# MCU.net
KiCad netlist of a schematic drawn in Altium Designer
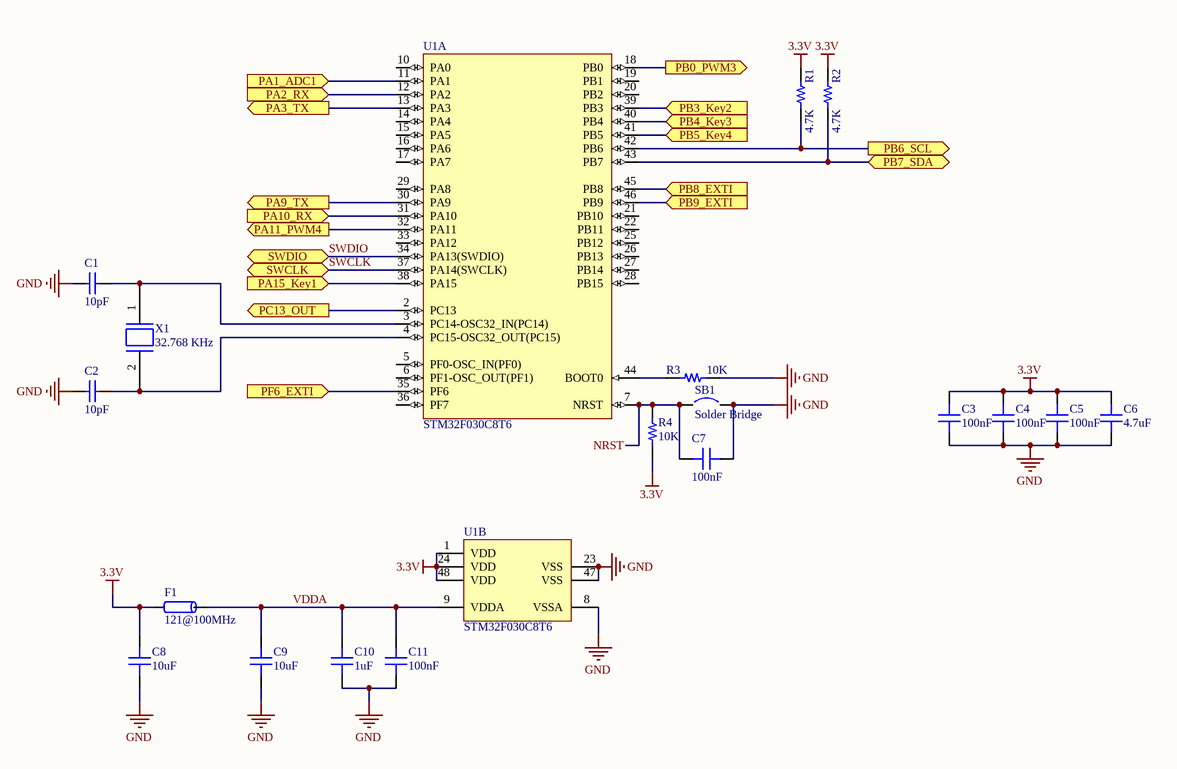
[diagram p0: MCU.SchDoc]

(export (version "E")
  (design (tool "Eeschema 10.0.6"))
  (components
    (comp (ref "C1")
      (value "10pF")
      (footprint "0603C")
      (description "Capacitor")
      (libsource (lib "NAHAL_LIB") (part "Cap"))
    )
    (comp (ref "C2")
      (value "10pF")
      (footprint "0603C")
      (description "Capacitor")
      (libsource (lib "NAHAL_LIB") (part "Cap"))
    )
    (comp (ref "C3")
      (value "100nF")
      (footprint "CAP 0603_1608")
      (description "SMT Capacitor")
      (libsource (lib "Capacitor") (part "Cap 0603"))
    )
    (comp (ref "C4")
      (value "100nF")
      (footprint "CAP 0603_1608")
      (description "SMT Capacitor")
      (libsource (lib "Capacitor") (part "Cap 0603"))
    )
    (comp (ref "C5")
      (value "100nF")
      (footprint "CAP 0603_1608")
      (description "SMT Capacitor")
      (libsource (lib "Capacitor") (part "Cap 0603"))
    )
    (comp (ref "C6")
      (value "4.7uF")
      (footprint "CAP 0603_1608")
      (description "SMT Capacitor")
      (libsource (lib "Capacitor") (part "Cap 0603"))
    )
    (comp (ref "C7")
      (value "100nF")
      (footprint "CAP 0603_1608")
      (description "SMT Capacitor")
      (libsource (lib "Capacitor") (part "Cap 0603"))
    )
    (comp (ref "C8")
      (value "10uF")
      (footprint "CAP 0603_1608")
      (description "SMT Capacitor")
      (libsource (lib "Capacitor") (part "Cap 0603"))
    )
    (comp (ref "C9")
      (value "10uF")
      (footprint "CAP 0603_1608")
      (description "SMT Capacitor")
      (libsource (lib "Capacitor") (part "Cap 0603"))
    )
    (comp (ref "C10")
      (value "1uF")
      (footprint "CAP 0603_1608")
      (description "SMT Capacitor")
      (libsource (lib "Capacitor") (part "Cap 0603"))
    )
    (comp (ref "C11")
      (value "100nF")
      (footprint "CAP 0603_1608")
      (description "SMT Capacitor")
      (libsource (lib "Capacitor") (part "Cap 0603"))
    )
    (comp (ref "F1")
      (value "121@100MHz")
      (footprint "Ferrite-0805")
      (description "Ferrite Bead")
      (libsource (lib "Salman_lib") (part "Ferrite Bead"))
    )
    (comp (ref "R1")
      (value "4.7K")
      (footprint "RES 0603_1608")
      (description "SMT Resistor")
      (libsource (lib "Resistor") (part "Res 0603"))
    )
    (comp (ref "R2")
      (value "4.7K")
      (footprint "RES 0603_1608")
      (description "SMT Resistor")
      (libsource (lib "Resistor") (part "Res 0603"))
    )
    (comp (ref "R3")
      (value "10K")
      (footprint "RES 0603_1608")
      (description "SMT Resistor")
      (libsource (lib "Resistor") (part "Res 0603"))
    )
    (comp (ref "R4")
      (value "10K")
      (footprint "RES 0603_1608")
      (description "SMT Resistor")
      (libsource (lib "Resistor") (part "Res 0603"))
    )
    (comp (ref "SB1")
      (value "Solder Bridge")
      (footprint "Solder Bridge")
      (libsource (lib "NAHAL_LIB") (part "Solder Bridge"))
    )
    (comp (ref "U1")
      (value "STM32F030C8T6")
      (footprint "LQFP-48 7x7MM P0.5MM")
      (libsource (lib "Mcu") (part "STM32F030C8T6"))
    )
    (comp (ref "X1")
      (value "32.768 KHz")
      (footprint "32.768 - Right")
      (libsource (lib "Salman_lib") (part "XTAL"))
    )
  )
  (nets
    (net (code "1") (name "/NRST") (class "Default")
      (node (ref "C7") (pin "2") (pinfunction "2_2") (pintype "passive"))
      (node (ref "R4") (pin "2") (pinfunction "2_2") (pintype "passive"))
      (node (ref "SB1") (pin "1") (pinfunction "1_1") (pintype "passive"))
      (node (ref "U1") (pin "7") (pinfunction "NRST_7") (pintype "bidirectional"))
    )
    (net (code "2") (name "/PA1_ADC1") (class "Default")
      (node (ref "U1") (pin "11") (pinfunction "PA1_11") (pintype "bidirectional"))
    )
    (net (code "3") (name "/PA2_RX") (class "Default")
      (node (ref "U1") (pin "12") (pinfunction "PA2_12") (pintype "bidirectional"))
    )
    (net (code "4") (name "/PA3_TX") (class "Default")
      (node (ref "U1") (pin "13") (pinfunction "PA3_13") (pintype "bidirectional"))
    )
    (net (code "5") (name "/PA9_TX") (class "Default")
      (node (ref "U1") (pin "30") (pinfunction "PA9_30") (pintype "bidirectional"))
    )
    (net (code "6") (name "/PA10_RX") (class "Default")
      (node (ref "U1") (pin "31") (pinfunction "PA10_31") (pintype "bidirectional"))
    )
    (net (code "7") (name "/PA11_PWM4") (class "Default")
      (node (ref "U1") (pin "32") (pinfunction "PA11_32") (pintype "bidirectional"))
    )
    (net (code "8") (name "/PA15_Key1") (class "Default")
      (node (ref "U1") (pin "38") (pinfunction "PA15_38") (pintype "bidirectional"))
    )
    (net (code "9") (name "/PB0_PWM3") (class "Default")
      (node (ref "U1") (pin "18") (pinfunction "PB0_18") (pintype "bidirectional"))
    )
    (net (code "10") (name "/PB3_Key2") (class "Default")
      (node (ref "U1") (pin "39") (pinfunction "PB3_39") (pintype "bidirectional"))
    )
    (net (code "11") (name "/PB4_Key3") (class "Default")
      (node (ref "U1") (pin "40") (pinfunction "PB4_40") (pintype "bidirectional"))
    )
    (net (code "12") (name "/PB5_Key4") (class "Default")
      (node (ref "U1") (pin "41") (pinfunction "PB5_41") (pintype "bidirectional"))
    )
    (net (code "13") (name "/PB6_SCL") (class "Default")
      (node (ref "R1") (pin "1") (pinfunction "1_1") (pintype "passive"))
      (node (ref "U1") (pin "42") (pinfunction "PB6_42") (pintype "bidirectional"))
    )
    (net (code "14") (name "/PB7_SDA") (class "Default")
      (node (ref "R2") (pin "1") (pinfunction "1_1") (pintype "passive"))
      (node (ref "U1") (pin "43") (pinfunction "PB7_43") (pintype "bidirectional"))
    )
    (net (code "15") (name "/PB8_EXTI") (class "Default")
      (node (ref "U1") (pin "45") (pinfunction "PB8_45") (pintype "bidirectional"))
    )
    (net (code "16") (name "/PB9_EXTI") (class "Default")
      (node (ref "U1") (pin "46") (pinfunction "PB9_46") (pintype "bidirectional"))
    )
    (net (code "17") (name "/PC13_OUT") (class "Default")
      (node (ref "U1") (pin "2") (pinfunction "PC13_2") (pintype "bidirectional"))
    )
    (net (code "18") (name "/PF6_EXTI") (class "Default")
      (node (ref "U1") (pin "35") (pinfunction "PF6_35") (pintype "bidirectional"))
    )
    (net (code "19") (name "/SWCLK") (class "Default")
      (node (ref "U1") (pin "37") (pinfunction "PA14(SWCLK)_37") (pintype "bidirectional"))
    )
    (net (code "20") (name "/SWDIO") (class "Default")
      (node (ref "U1") (pin "34") (pinfunction "PA13(SWDIO)_34") (pintype "bidirectional"))
    )
    (net (code "21") (name "/VDDA") (class "Default")
      (node (ref "C10") (pin "2") (pinfunction "2_2") (pintype "passive"))
      (node (ref "C11") (pin "2") (pinfunction "2_2") (pintype "passive"))
      (node (ref "C9") (pin "2") (pinfunction "2_2") (pintype "passive"))
      (node (ref "F1") (pin "2") (pinfunction "66_2") (pintype "passive"))
      (node (ref "U1") (pin "9") (pinfunction "VDDA_9") (pintype "power_in"))
    )
    (net (code "22") (name "3.3V") (class "Default")
      (node (ref "C3") (pin "2") (pinfunction "2_2") (pintype "passive"))
      (node (ref "C4") (pin "2") (pinfunction "2_2") (pintype "passive"))
      (node (ref "C5") (pin "2") (pinfunction "2_2") (pintype "passive"))
      (node (ref "C6") (pin "2") (pinfunction "2_2") (pintype "passive"))
      (node (ref "C8") (pin "2") (pinfunction "2_2") (pintype "passive"))
      (node (ref "F1") (pin "1") (pinfunction "67_1") (pintype "passive"))
      (node (ref "R1") (pin "2") (pinfunction "2_2") (pintype "passive"))
      (node (ref "R2") (pin "2") (pinfunction "2_2") (pintype "passive"))
      (node (ref "R4") (pin "1") (pinfunction "1_1") (pintype "passive"))
      (node (ref "U1") (pin "1") (pinfunction "VDD_1") (pintype "power_in"))
      (node (ref "U1") (pin "24") (pinfunction "VDD_24") (pintype "power_in"))
      (node (ref "U1") (pin "48") (pinfunction "VDD_48") (pintype "power_in"))
    )
    (net (code "23") (name "GND") (class "Default")
      (node (ref "C1") (pin "1") (pinfunction "1_1") (pintype "passive"))
      (node (ref "C10") (pin "1") (pinfunction "1_1") (pintype "passive"))
      (node (ref "C11") (pin "1") (pinfunction "1_1") (pintype "passive"))
      (node (ref "C2") (pin "1") (pinfunction "1_1") (pintype "passive"))
      (node (ref "C3") (pin "1") (pinfunction "1_1") (pintype "passive"))
      (node (ref "C4") (pin "1") (pinfunction "1_1") (pintype "passive"))
      (node (ref "C5") (pin "1") (pinfunction "1_1") (pintype "passive"))
      (node (ref "C6") (pin "1") (pinfunction "1_1") (pintype "passive"))
      (node (ref "C7") (pin "1") (pinfunction "1_1") (pintype "passive"))
      (node (ref "C8") (pin "1") (pinfunction "1_1") (pintype "passive"))
      (node (ref "C9") (pin "1") (pinfunction "1_1") (pintype "passive"))
      (node (ref "R3") (pin "2") (pinfunction "2_2") (pintype "passive"))
      (node (ref "SB1") (pin "2") (pinfunction "2_2") (pintype "passive"))
      (node (ref "U1") (pin "23") (pinfunction "VSS_23") (pintype "power_in"))
      (node (ref "U1") (pin "47") (pinfunction "VSS_47") (pintype "power_in"))
      (node (ref "U1") (pin "8") (pinfunction "VSSA_8") (pintype "power_in"))
    )
    (net (code "24") (name "Net-(U1A-BOOT0)") (class "Default")
      (node (ref "R3") (pin "1") (pinfunction "1_1") (pintype "passive"))
      (node (ref "U1") (pin "44") (pinfunction "BOOT0_44") (pintype "input"))
    )
    (net (code "25") (name "Net-(U1A-PC14-OSC32_IN(PC14))") (class "Default")
      (node (ref "C1") (pin "2") (pinfunction "2_2") (pintype "passive"))
      (node (ref "U1") (pin "3") (pinfunction "PC14-OSC32_IN(PC14)_3") (pintype "bidirectional"))
      (node (ref "X1") (pin "1") (pintype "passive"))
    )
    (net (code "26") (name "Net-(U1A-PC15-OSC32_OUT(PC15))") (class "Default")
      (node (ref "C2") (pin "2") (pinfunction "2_2") (pintype "passive"))
      (node (ref "U1") (pin "4") (pinfunction "PC15-OSC32_OUT(PC15)_4") (pintype "bidirectional"))
      (node (ref "X1") (pin "2") (pintype "passive"))
    )
    (net (code "27") (name "unconnected-(U1A-PA0-Pad10)") (class "Default")
      (node (ref "U1") (pin "10") (pinfunction "PA0_10") (pintype "bidirectional"))
    )
    (net (code "28") (name "unconnected-(U1A-PA4-Pad14)") (class "Default")
      (node (ref "U1") (pin "14") (pinfunction "PA4_14") (pintype "bidirectional"))
    )
    (net (code "29") (name "unconnected-(U1A-PA5-Pad15)") (class "Default")
      (node (ref "U1") (pin "15") (pinfunction "PA5_15") (pintype "bidirectional"))
    )
    (net (code "30") (name "unconnected-(U1A-PA6-Pad16)") (class "Default")
      (node (ref "U1") (pin "16") (pinfunction "PA6_16") (pintype "bidirectional"))
    )
    (net (code "31") (name "unconnected-(U1A-PA7-Pad17)") (class "Default")
      (node (ref "U1") (pin "17") (pinfunction "PA7_17") (pintype "bidirectional"))
    )
    (net (code "32") (name "unconnected-(U1A-PA8-Pad29)") (class "Default")
      (node (ref "U1") (pin "29") (pinfunction "PA8_29") (pintype "bidirectional"))
    )
    (net (code "33") (name "unconnected-(U1A-PA12-Pad33)") (class "Default")
      (node (ref "U1") (pin "33") (pinfunction "PA12_33") (pintype "bidirectional"))
    )
    (net (code "34") (name "unconnected-(U1A-PB1-Pad19)") (class "Default")
      (node (ref "U1") (pin "19") (pinfunction "PB1_19") (pintype "bidirectional"))
    )
    (net (code "35") (name "unconnected-(U1A-PB2-Pad20)") (class "Default")
      (node (ref "U1") (pin "20") (pinfunction "PB2_20") (pintype "bidirectional"))
    )
    (net (code "36") (name "unconnected-(U1A-PB10-Pad21)") (class "Default")
      (node (ref "U1") (pin "21") (pinfunction "PB10_21") (pintype "bidirectional"))
    )
    (net (code "37") (name "unconnected-(U1A-PB11-Pad22)") (class "Default")
      (node (ref "U1") (pin "22") (pinfunction "PB11_22") (pintype "bidirectional"))
    )
    (net (code "38") (name "unconnected-(U1A-PB12-Pad25)") (class "Default")
      (node (ref "U1") (pin "25") (pinfunction "PB12_25") (pintype "bidirectional"))
    )
    (net (code "39") (name "unconnected-(U1A-PB13-Pad26)") (class "Default")
      (node (ref "U1") (pin "26") (pinfunction "PB13_26") (pintype "bidirectional"))
    )
    (net (code "40") (name "unconnected-(U1A-PB14-Pad27)") (class "Default")
      (node (ref "U1") (pin "27") (pinfunction "PB14_27") (pintype "bidirectional"))
    )
    (net (code "41") (name "unconnected-(U1A-PB15-Pad28)") (class "Default")
      (node (ref "U1") (pin "28") (pinfunction "PB15_28") (pintype "bidirectional"))
    )
    (net (code "42") (name "unconnected-(U1A-PF0-OSC_IN(PF0)-Pad5)") (class "Default")
      (node (ref "U1") (pin "5") (pinfunction "PF0-OSC_IN(PF0)_5") (pintype "bidirectional"))
    )
    (net (code "43") (name "unconnected-(U1A-PF1-OSC_OUT(PF1)-Pad6)") (class "Default")
      (node (ref "U1") (pin "6") (pinfunction "PF1-OSC_OUT(PF1)_6") (pintype "bidirectional"))
    )
    (net (code "44") (name "unconnected-(U1A-PF7-Pad36)") (class "Default")
      (node (ref "U1") (pin "36") (pinfunction "PF7_36") (pintype "bidirectional"))
    )
  )
)
